# tick-mk-4_2.net
KiCad netlist of a schematic drawn in EAGLE
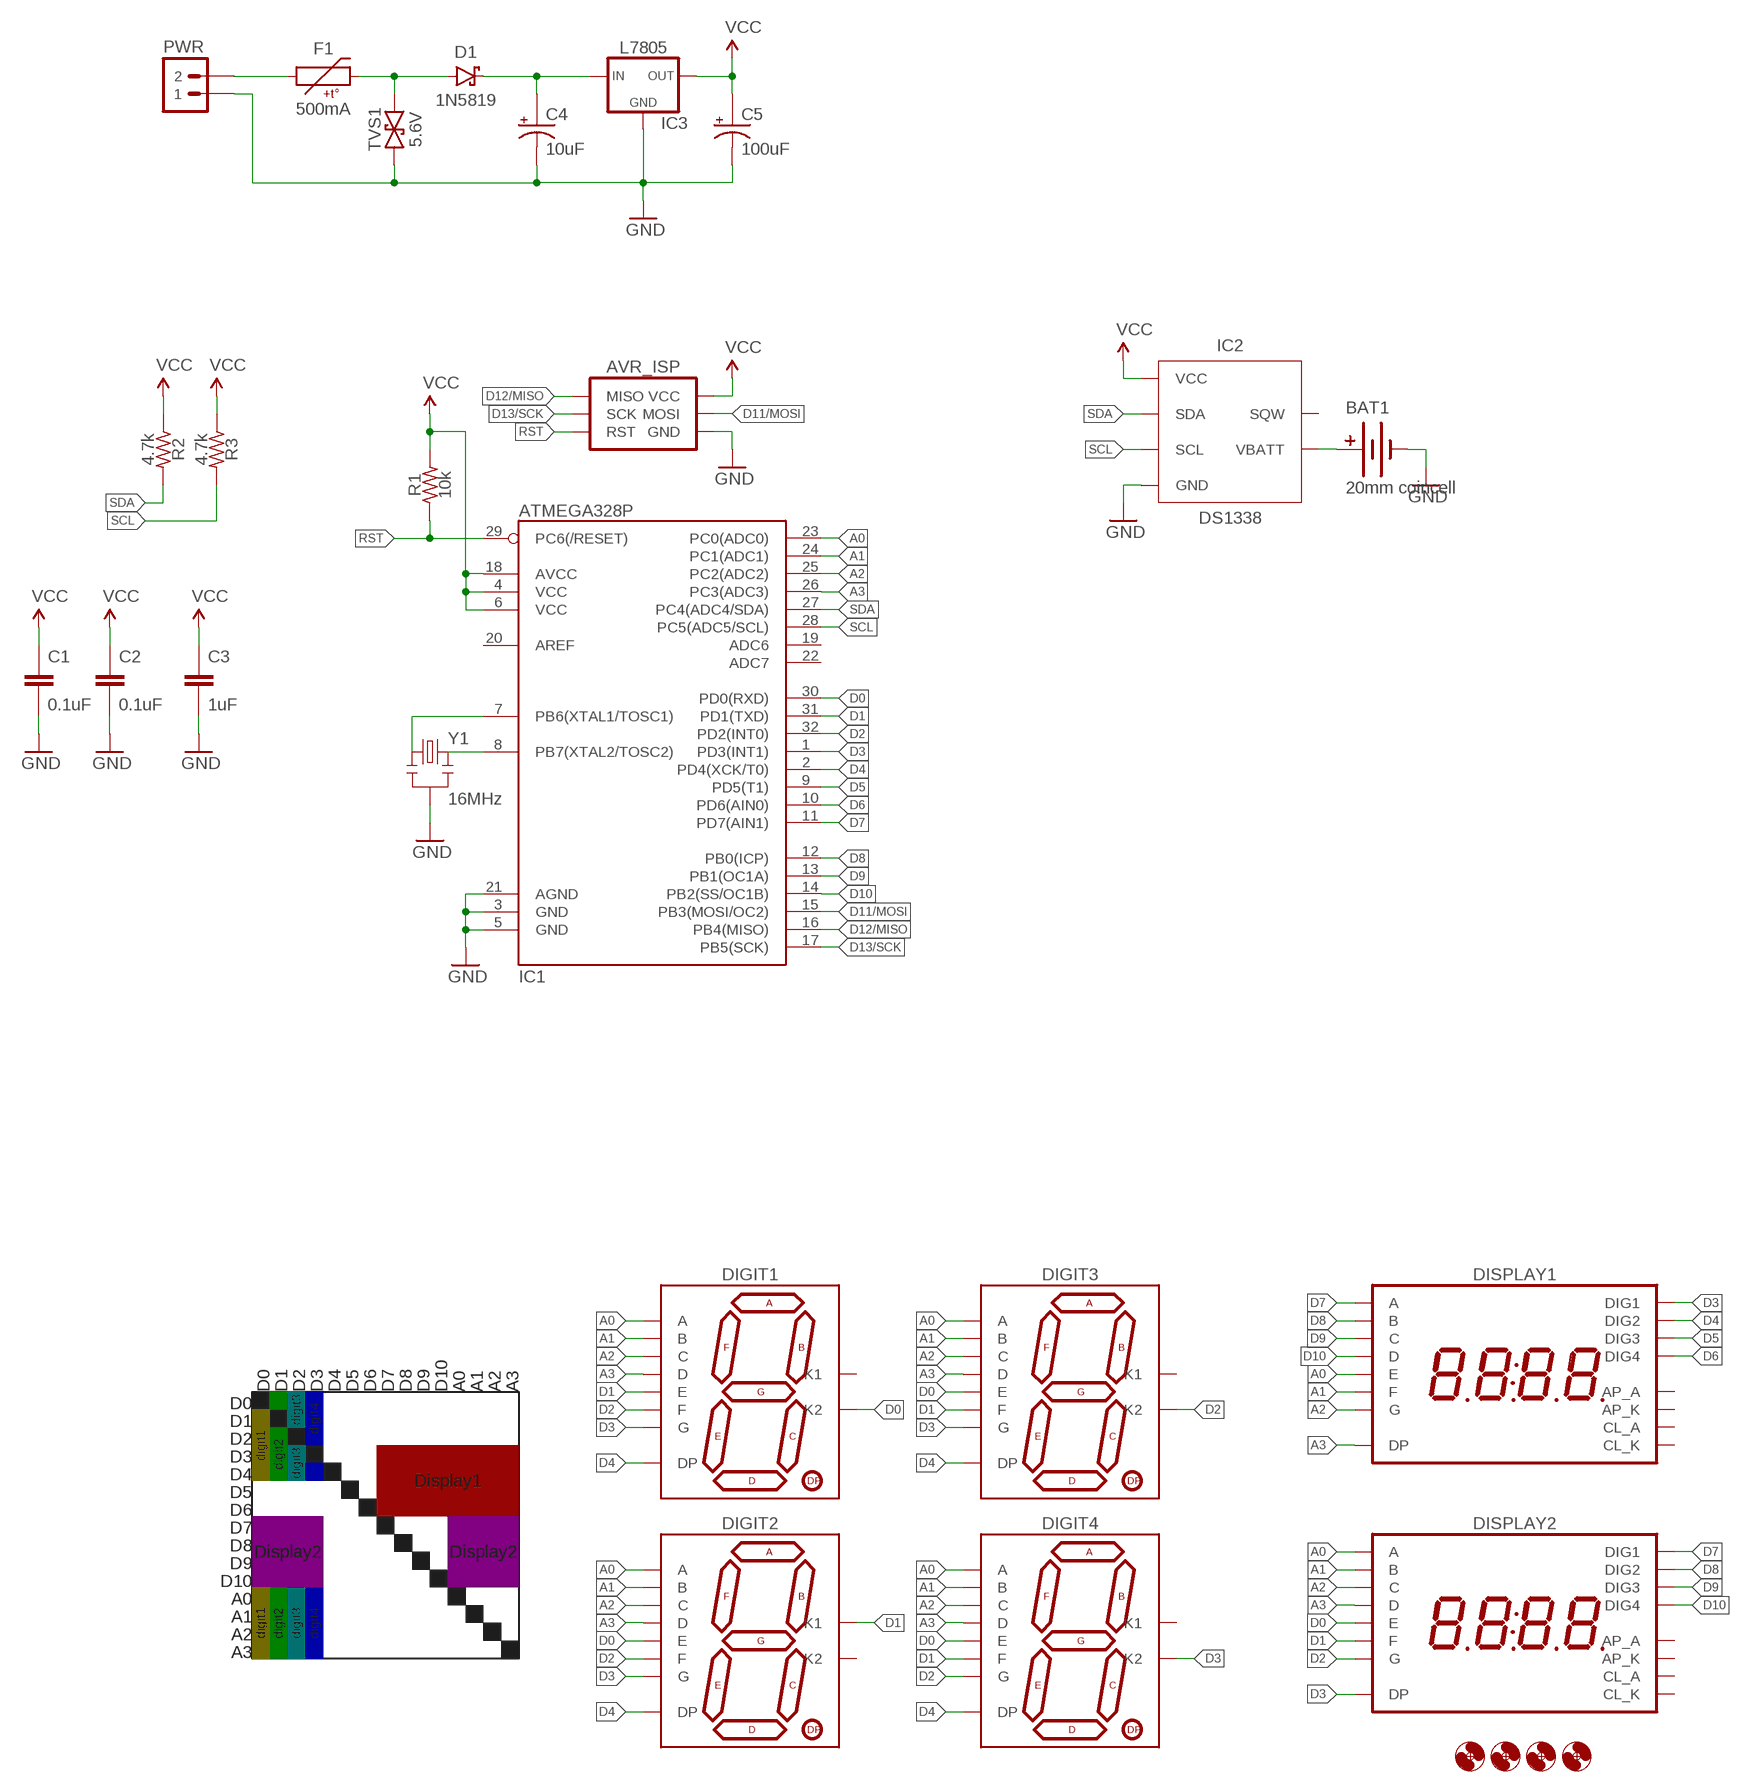
[diagram p0: schematic, sheet 1]

(export (version "E")
  (design (tool "Eeschema 10.0.6"))
  (components
    (comp (ref "AVR_ISP")
      (value "AVR_SPI_PRG_6PTH")
      (footprint "eagle-import:2X3")
      (libsource (lib "eagle-import") (part "AVR_SPI_PRG_6PTH"))
    )
    (comp (ref "BAT1")
      (value "20mm coincell")
      (footprint "eagle-import:BATTCON_20MM_MINE")
      (libsource (lib "eagle-import") (part "BATTERY20MMSMD-MINE"))
    )
    (comp (ref "C1")
      (value "0.1uF")
      (footprint "eagle-import:C025-024X044")
      (libsource (lib "eagle-import") (part "CAPACITOR-CERAMIC025-024X044"))
    )
    (comp (ref "C2")
      (value "0.1uF")
      (footprint "eagle-import:C025-024X044")
      (libsource (lib "eagle-import") (part "CAPACITOR-CERAMIC025-024X044"))
    )
    (comp (ref "C3")
      (value "1uF")
      (footprint "eagle-import:C025-024X044")
      (libsource (lib "eagle-import") (part "CAPACITOR-CERAMIC025-024X044"))
    )
    (comp (ref "C4")
      (value "10uF")
      (footprint "eagle-import:E2-5")
      (libsource (lib "eagle-import") (part "CAPACITOR-POLARIZEDE2-5"))
    )
    (comp (ref "C5")
      (value "100uF")
      (footprint "eagle-import:E2,5-6")
      (libsource (lib "eagle-import") (part "CAPACITOR-POLARIZEDE2.5-6"))
    )
    (comp (ref "D1")
      (value "1N5819")
      (footprint "eagle-import:DIODE-10.16MM")
      (libsource (lib "eagle-import") (part "DIODE-SCHOTTKYPTH-10.16MM"))
    )
    (comp (ref "DIGIT1")
      (value "7SEG_1DIGPTH-25.4MM-BARE")
      (footprint "eagle-import:7SEG_1DIG_25.4MM_NOSILK")
      (libsource (lib "eagle-import") (part "7SEG_1DIGPTH-25.4MM-BARE"))
    )
    (comp (ref "DIGIT2")
      (value "7SEG_1DIGPTH-25.4MM-BARE")
      (footprint "eagle-import:7SEG_1DIG_25.4MM_NOSILK")
      (libsource (lib "eagle-import") (part "7SEG_1DIGPTH-25.4MM-BARE"))
    )
    (comp (ref "DIGIT3")
      (value "7SEG_1DIGPTH-25.4MM-BARE")
      (footprint "eagle-import:7SEG_1DIG_25.4MM_NOSILK")
      (libsource (lib "eagle-import") (part "7SEG_1DIGPTH-25.4MM-BARE"))
    )
    (comp (ref "DIGIT4")
      (value "7SEG_1DIGPTH-25.4MM-BARE")
      (footprint "eagle-import:7SEG_1DIG_25.4MM_NOSILK")
      (libsource (lib "eagle-import") (part "7SEG_1DIGPTH-25.4MM-BARE"))
    )
    (comp (ref "DISPLAY1")
      (value "7SEG_4DIGIT_COLON_APOS")
      (footprint "eagle-import:7SEG_4DIG_10MM")
      (libsource (lib "eagle-import") (part "7SEG_4DIGIT_COLON_APOS"))
    )
    (comp (ref "DISPLAY2")
      (value "7SEG_4DIGIT_COLON_APOS")
      (footprint "eagle-import:7SEG_4DIG_10MM")
      (libsource (lib "eagle-import") (part "7SEG_4DIGIT_COLON_APOS"))
    )
    (comp (ref "F1")
      (value "500mA")
      (footprint "eagle-import:PTC-PTH-5.08MM")
      (libsource (lib "eagle-import") (part "PTCPTH-5.08MM"))
    )
    (comp (ref "H1")
      (value "HOLE#2")
      (footprint "eagle-import:HOLE-#2")
      (libsource (lib "eagle-import") (part "HOLE#2"))
    )
    (comp (ref "H2")
      (value "HOLE#2")
      (footprint "eagle-import:HOLE-#2")
      (libsource (lib "eagle-import") (part "HOLE#2"))
    )
    (comp (ref "H3")
      (value "HOLE#2")
      (footprint "eagle-import:HOLE-#2")
      (libsource (lib "eagle-import") (part "HOLE#2"))
    )
    (comp (ref "H4")
      (value "HOLE#2")
      (footprint "eagle-import:HOLE-#2")
      (libsource (lib "eagle-import") (part "HOLE#2"))
    )
    (comp (ref "IC1")
      (value "ATMEGA328P")
      (footprint "eagle-import:TQFP32-08")
      (libsource (lib "eagle-import") (part "ATMEGA328_SMT"))
    )
    (comp (ref "IC2")
      (value "DS1338")
      (footprint "eagle-import:SO16W")
      (libsource (lib "eagle-import") (part "DS1338CSOIC16W"))
    )
    (comp (ref "IC3")
      (value "L7805")
      (footprint "eagle-import:TO220-IGO-THERMPAD")
      (libsource (lib "eagle-import") (part "V_REG_78XXTO-220-THERMPAD"))
    )
    (comp (ref "PWR")
      (value "M02JST-PTH-VERT")
      (footprint "eagle-import:JST-2-PH-VERT-PTH")
      (libsource (lib "eagle-import") (part "M02JST-PTH-VERT"))
    )
    (comp (ref "R1")
      (value "10k")
      (footprint "eagle-import:RESISTOR-AXIAL-PTH-6.35MM")
      (libsource (lib "eagle-import") (part "RESISTORPTH-AXIAL-6.35MM"))
    )
    (comp (ref "R2")
      (value "4.7k")
      (footprint "eagle-import:RESISTOR-AXIAL-PTH-6.35MM")
      (libsource (lib "eagle-import") (part "RESISTORPTH-AXIAL-6.35MM"))
    )
    (comp (ref "R3")
      (value "4.7k")
      (footprint "eagle-import:RESISTOR-AXIAL-PTH-6.35MM")
      (libsource (lib "eagle-import") (part "RESISTORPTH-AXIAL-6.35MM"))
    )
    (comp (ref "TVS1")
      (value "5.6V")
      (footprint "eagle-import:DO-41-TVS-BI-10.16MM")
      (libsource (lib "eagle-import") (part "TVSDO-41-10.16MM"))
    )
    (comp (ref "Y1")
      (value "16MHz")
      (footprint "eagle-import:RESONATOR-PTH")
      (libsource (lib "eagle-import") (part "RESONATORPTH"))
    )
  )
  (nets
    (net (code "1") (name "A0") (class "Default")
      (node (ref "DIGIT1") (pin "7") (pinfunction "A_7") (pintype "bidirectional"))
      (node (ref "DIGIT2") (pin "7") (pinfunction "A_7") (pintype "bidirectional"))
      (node (ref "DIGIT3") (pin "7") (pinfunction "A_7") (pintype "bidirectional"))
      (node (ref "DIGIT4") (pin "7") (pinfunction "A_7") (pintype "bidirectional"))
      (node (ref "DISPLAY1") (pin "5") (pinfunction "E_5") (pintype "passive"))
      (node (ref "DISPLAY2") (pin "14") (pinfunction "A_14") (pintype "passive"))
      (node (ref "IC1") (pin "23") (pinfunction "PC0(ADC0)_23") (pintype "bidirectional"))
    )
    (net (code "2") (name "A1") (class "Default")
      (node (ref "DIGIT1") (pin "6") (pinfunction "B_6") (pintype "bidirectional"))
      (node (ref "DIGIT2") (pin "6") (pinfunction "B_6") (pintype "bidirectional"))
      (node (ref "DIGIT3") (pin "6") (pinfunction "B_6") (pintype "bidirectional"))
      (node (ref "DIGIT4") (pin "6") (pinfunction "B_6") (pintype "bidirectional"))
      (node (ref "DISPLAY1") (pin "11") (pinfunction "F_11") (pintype "passive"))
      (node (ref "DISPLAY2") (pin "16") (pinfunction "B_16") (pintype "passive"))
      (node (ref "IC1") (pin "24") (pinfunction "PC1(ADC1)_24") (pintype "bidirectional"))
    )
    (net (code "3") (name "A2") (class "Default")
      (node (ref "DIGIT1") (pin "4") (pinfunction "C_4") (pintype "bidirectional"))
      (node (ref "DIGIT2") (pin "4") (pinfunction "C_4") (pintype "bidirectional"))
      (node (ref "DIGIT3") (pin "4") (pinfunction "C_4") (pintype "bidirectional"))
      (node (ref "DIGIT4") (pin "4") (pinfunction "C_4") (pintype "bidirectional"))
      (node (ref "DISPLAY1") (pin "15") (pinfunction "G_15") (pintype "passive"))
      (node (ref "DISPLAY2") (pin "13") (pinfunction "C_13") (pintype "passive"))
      (node (ref "IC1") (pin "25") (pinfunction "PC2(ADC2)_25") (pintype "bidirectional"))
    )
    (net (code "4") (name "A3") (class "Default")
      (node (ref "DIGIT1") (pin "2") (pinfunction "D_2") (pintype "bidirectional"))
      (node (ref "DIGIT2") (pin "2") (pinfunction "D_2") (pintype "bidirectional"))
      (node (ref "DIGIT3") (pin "2") (pinfunction "D_2") (pintype "bidirectional"))
      (node (ref "DIGIT4") (pin "2") (pinfunction "D_2") (pintype "bidirectional"))
      (node (ref "DISPLAY1") (pin "7") (pinfunction "DP_7") (pintype "passive"))
      (node (ref "DISPLAY2") (pin "3") (pinfunction "D_3") (pintype "passive"))
      (node (ref "IC1") (pin "26") (pinfunction "PC3(ADC3)_26") (pintype "bidirectional"))
    )
    (net (code "5") (name "D0") (class "Default")
      (node (ref "DIGIT1") (pin "8") (pinfunction "K2_8") (pintype "bidirectional"))
      (node (ref "DIGIT2") (pin "1") (pinfunction "E_1") (pintype "bidirectional"))
      (node (ref "DIGIT3") (pin "1") (pinfunction "E_1") (pintype "bidirectional"))
      (node (ref "DIGIT4") (pin "1") (pinfunction "E_1") (pintype "bidirectional"))
      (node (ref "DISPLAY2") (pin "5") (pinfunction "E_5") (pintype "passive"))
      (node (ref "IC1") (pin "30") (pinfunction "PD0(RXD)_30") (pintype "bidirectional"))
    )
    (net (code "6") (name "D1") (class "Default")
      (node (ref "DIGIT1") (pin "1") (pinfunction "E_1") (pintype "bidirectional"))
      (node (ref "DIGIT2") (pin "3") (pinfunction "K1_3") (pintype "bidirectional"))
      (node (ref "DIGIT3") (pin "9") (pinfunction "F_9") (pintype "bidirectional"))
      (node (ref "DIGIT4") (pin "9") (pinfunction "F_9") (pintype "bidirectional"))
      (node (ref "DISPLAY2") (pin "11") (pinfunction "F_11") (pintype "passive"))
      (node (ref "IC1") (pin "31") (pinfunction "PD1(TXD)_31") (pintype "bidirectional"))
    )
    (net (code "7") (name "D2") (class "Default")
      (node (ref "DIGIT1") (pin "9") (pinfunction "F_9") (pintype "bidirectional"))
      (node (ref "DIGIT2") (pin "9") (pinfunction "F_9") (pintype "bidirectional"))
      (node (ref "DIGIT3") (pin "8") (pinfunction "K2_8") (pintype "bidirectional"))
      (node (ref "DIGIT4") (pin "10") (pinfunction "G_10") (pintype "bidirectional"))
      (node (ref "DISPLAY2") (pin "15") (pinfunction "G_15") (pintype "passive"))
      (node (ref "IC1") (pin "32") (pinfunction "PD2(INT0)_32") (pintype "bidirectional"))
    )
    (net (code "8") (name "D3") (class "Default")
      (node (ref "DIGIT1") (pin "10") (pinfunction "G_10") (pintype "bidirectional"))
      (node (ref "DIGIT2") (pin "10") (pinfunction "G_10") (pintype "bidirectional"))
      (node (ref "DIGIT3") (pin "10") (pinfunction "G_10") (pintype "bidirectional"))
      (node (ref "DIGIT4") (pin "8") (pinfunction "K2_8") (pintype "bidirectional"))
      (node (ref "DISPLAY1") (pin "1") (pinfunction "DIG1_1") (pintype "passive"))
      (node (ref "DISPLAY2") (pin "7") (pinfunction "DP_7") (pintype "passive"))
      (node (ref "IC1") (pin "1") (pinfunction "PD3(INT1)_1") (pintype "bidirectional"))
    )
    (net (code "9") (name "D4") (class "Default")
      (node (ref "DIGIT1") (pin "5") (pinfunction "DP_5") (pintype "bidirectional"))
      (node (ref "DIGIT2") (pin "5") (pinfunction "DP_5") (pintype "bidirectional"))
      (node (ref "DIGIT3") (pin "5") (pinfunction "DP_5") (pintype "bidirectional"))
      (node (ref "DIGIT4") (pin "5") (pinfunction "DP_5") (pintype "bidirectional"))
      (node (ref "DISPLAY1") (pin "2") (pinfunction "DIG2_2") (pintype "passive"))
      (node (ref "IC1") (pin "2") (pinfunction "PD4(XCK/T0)_2") (pintype "bidirectional"))
    )
    (net (code "10") (name "D5") (class "Default")
      (node (ref "DISPLAY1") (pin "6") (pinfunction "DIG3_6") (pintype "passive"))
      (node (ref "IC1") (pin "9") (pinfunction "PD5(T1)_9") (pintype "bidirectional"))
    )
    (net (code "11") (name "D6") (class "Default")
      (node (ref "DISPLAY1") (pin "8") (pinfunction "DIG4_8") (pintype "passive"))
      (node (ref "IC1") (pin "10") (pinfunction "PD6(AIN0)_10") (pintype "bidirectional"))
    )
    (net (code "12") (name "D7") (class "Default")
      (node (ref "DISPLAY1") (pin "14") (pinfunction "A_14") (pintype "passive"))
      (node (ref "DISPLAY2") (pin "1") (pinfunction "DIG1_1") (pintype "passive"))
      (node (ref "IC1") (pin "11") (pinfunction "PD7(AIN1)_11") (pintype "bidirectional"))
    )
    (net (code "13") (name "D8") (class "Default")
      (node (ref "DISPLAY1") (pin "16") (pinfunction "B_16") (pintype "passive"))
      (node (ref "DISPLAY2") (pin "2") (pinfunction "DIG2_2") (pintype "passive"))
      (node (ref "IC1") (pin "12") (pinfunction "PB0(ICP)_12") (pintype "bidirectional"))
    )
    (net (code "14") (name "D9") (class "Default")
      (node (ref "DISPLAY1") (pin "13") (pinfunction "C_13") (pintype "passive"))
      (node (ref "DISPLAY2") (pin "6") (pinfunction "DIG3_6") (pintype "passive"))
      (node (ref "IC1") (pin "13") (pinfunction "PB1(OC1A)_13") (pintype "bidirectional"))
    )
    (net (code "15") (name "D10") (class "Default")
      (node (ref "DISPLAY1") (pin "3") (pinfunction "D_3") (pintype "passive"))
      (node (ref "DISPLAY2") (pin "8") (pinfunction "DIG4_8") (pintype "passive"))
      (node (ref "IC1") (pin "14") (pinfunction "PB2(SS/OC1B)_14") (pintype "bidirectional"))
    )
    (net (code "16") (name "D11{slash}MOSI") (class "Default")
      (node (ref "AVR_ISP") (pin "4") (pinfunction "MOSI_4") (pintype "passive"))
      (node (ref "IC1") (pin "15") (pinfunction "PB3(MOSI/OC2)_15") (pintype "bidirectional"))
    )
    (net (code "17") (name "D12{slash}MISO") (class "Default")
      (node (ref "AVR_ISP") (pin "1") (pinfunction "MISO_1") (pintype "passive"))
      (node (ref "IC1") (pin "16") (pinfunction "PB4(MISO)_16") (pintype "bidirectional"))
    )
    (net (code "18") (name "D13{slash}SCK") (class "Default")
      (node (ref "AVR_ISP") (pin "3") (pinfunction "SCK_3") (pintype "passive"))
      (node (ref "IC1") (pin "17") (pinfunction "PB5(SCK)_17") (pintype "bidirectional"))
    )
    (net (code "19") (name "GND") (class "Default")
      (node (ref "AVR_ISP") (pin "6") (pinfunction "GND_6") (pintype "passive"))
      (node (ref "BAT1") (pin "BOTTOM") (pinfunction "-_BOTTOM") (pintype "power_in"))
      (node (ref "C1") (pin "2") (pinfunction "2_2") (pintype "passive"))
      (node (ref "C2") (pin "2") (pinfunction "2_2") (pintype "passive"))
      (node (ref "C3") (pin "2") (pinfunction "2_2") (pintype "passive"))
      (node (ref "C4") (pin "-") (pinfunction "-_-") (pintype "passive"))
      (node (ref "C5") (pin "-") (pinfunction "-_-") (pintype "passive"))
      (node (ref "IC1") (pin "21") (pinfunction "AGND_21") (pintype "bidirectional"))
      (node (ref "IC1") (pin "3") (pinfunction "GND_3") (pintype "bidirectional"))
      (node (ref "IC1") (pin "5") (pinfunction "GND_5") (pintype "bidirectional"))
      (node (ref "IC2") (pin "10") (pinfunction "GND_10") (pintype "bidirectional"))
      (node (ref "IC2") (pin "11") (pinfunction "GND_11") (pintype "bidirectional"))
      (node (ref "IC2") (pin "12") (pinfunction "GND_12") (pintype "bidirectional"))
      (node (ref "IC2") (pin "13") (pinfunction "GND_13") (pintype "bidirectional"))
      (node (ref "IC2") (pin "15") (pinfunction "GND_15") (pintype "bidirectional"))
      (node (ref "IC2") (pin "4") (pinfunction "GND_4") (pintype "bidirectional"))
      (node (ref "IC2") (pin "5") (pinfunction "GND_5") (pintype "bidirectional"))
      (node (ref "IC2") (pin "6") (pinfunction "GND_6") (pintype "bidirectional"))
      (node (ref "IC2") (pin "7") (pinfunction "GND_7") (pintype "bidirectional"))
      (node (ref "IC2") (pin "8") (pinfunction "GND_8") (pintype "bidirectional"))
      (node (ref "IC2") (pin "9") (pinfunction "GND_9") (pintype "bidirectional"))
      (node (ref "IC3") (pin "4") (pinfunction "GND_4") (pintype "bidirectional"))
      (node (ref "IC3") (pin "GND") (pinfunction "GND_GND") (pintype "bidirectional"))
      (node (ref "PWR") (pin "1") (pinfunction "1_1") (pintype "passive"))
      (node (ref "TVS1") (pin "P$1") (pinfunction "1_P$1") (pintype "passive"))
      (node (ref "Y1") (pin "2") (pinfunction "2_2") (pintype "passive"))
    )
    (net (code "20") (name "Net-(C4-Pad+)") (class "Default")
      (node (ref "C4") (pin "+") (pinfunction "+_+") (pintype "passive"))
      (node (ref "D1") (pin "C") (pinfunction "C_C") (pintype "passive"))
      (node (ref "IC3") (pin "IN") (pinfunction "IN_IN") (pintype "bidirectional"))
    )
    (net (code "21") (name "Net-(F1-1)") (class "Default")
      (node (ref "F1") (pin "P$1") (pinfunction "1_P$1") (pintype "passive"))
      (node (ref "PWR") (pin "2") (pinfunction "2_2") (pintype "passive"))
    )
    (net (code "22") (name "Net-(F1-2)") (class "Default")
      (node (ref "D1") (pin "A") (pinfunction "A_A") (pintype "passive"))
      (node (ref "F1") (pin "P$2") (pinfunction "2_P$2") (pintype "passive"))
      (node (ref "TVS1") (pin "P$2") (pinfunction "2_P$2") (pintype "passive"))
    )
    (net (code "23") (name "Net-(IC1-PB6(XTAL1{slash}TOSC1))") (class "Default")
      (node (ref "IC1") (pin "7") (pinfunction "PB6(XTAL1/TOSC1)_7") (pintype "bidirectional"))
      (node (ref "Y1") (pin "1") (pinfunction "1_1") (pintype "passive"))
    )
    (net (code "24") (name "Net-(IC1-PB7(XTAL2{slash}TOSC2))") (class "Default")
      (node (ref "IC1") (pin "8") (pinfunction "PB7(XTAL2/TOSC2)_8") (pintype "bidirectional"))
      (node (ref "Y1") (pin "3") (pinfunction "3_3") (pintype "passive"))
    )
    (net (code "25") (name "Net-(IC2-VBATT)") (class "Default")
      (node (ref "BAT1") (pin "TOP@1") (pinfunction "+_TOP@1") (pintype "power_in"))
      (node (ref "BAT1") (pin "TOP@2") (pinfunction "+_TOP@2") (pintype "power_in"))
      (node (ref "IC2") (pin "14") (pinfunction "VBATT_14") (pintype "bidirectional"))
    )
    (net (code "26") (name "RST") (class "Default")
      (node (ref "AVR_ISP") (pin "5") (pinfunction "RST_5") (pintype "passive"))
      (node (ref "IC1") (pin "29") (pinfunction "PC6(/RESET)_29") (pintype "bidirectional"))
      (node (ref "R1") (pin "P$1") (pinfunction "1_P$1") (pintype "passive"))
    )
    (net (code "27") (name "SCL") (class "Default")
      (node (ref "IC1") (pin "28") (pinfunction "PC5(ADC5/SCL)_28") (pintype "bidirectional"))
      (node (ref "IC2") (pin "1") (pinfunction "SCL_1") (pintype "bidirectional"))
      (node (ref "R3") (pin "P$2") (pinfunction "2_P$2") (pintype "passive"))
    )
    (net (code "28") (name "SDA") (class "Default")
      (node (ref "IC1") (pin "27") (pinfunction "PC4(ADC4/SDA)_27") (pintype "bidirectional"))
      (node (ref "IC2") (pin "16") (pinfunction "SDA_16") (pintype "bidirectional"))
      (node (ref "R2") (pin "P$2") (pinfunction "2_P$2") (pintype "passive"))
    )
    (net (code "29") (name "VCC") (class "Default")
      (node (ref "AVR_ISP") (pin "2") (pinfunction "VCC_2") (pintype "passive"))
      (node (ref "C1") (pin "1") (pinfunction "1_1") (pintype "passive"))
      (node (ref "C2") (pin "1") (pinfunction "1_1") (pintype "passive"))
      (node (ref "C3") (pin "1") (pinfunction "1_1") (pintype "passive"))
      (node (ref "C5") (pin "+") (pinfunction "+_+") (pintype "passive"))
      (node (ref "IC1") (pin "18") (pinfunction "AVCC_18") (pintype "bidirectional"))
      (node (ref "IC1") (pin "4") (pinfunction "VCC_4") (pintype "bidirectional"))
      (node (ref "IC1") (pin "6") (pinfunction "VCC_6") (pintype "bidirectional"))
      (node (ref "IC2") (pin "3") (pinfunction "VCC_3") (pintype "bidirectional"))
      (node (ref "IC3") (pin "OUT") (pinfunction "OUT_OUT") (pintype "bidirectional"))
      (node (ref "R1") (pin "P$2") (pinfunction "2_P$2") (pintype "passive"))
      (node (ref "R2") (pin "P$1") (pinfunction "1_P$1") (pintype "passive"))
      (node (ref "R3") (pin "P$1") (pinfunction "1_P$1") (pintype "passive"))
    )
    (net (code "30") (name "unconnected-(DIGIT1-K1-Pad3)") (class "Default")
      (node (ref "DIGIT1") (pin "3") (pinfunction "K1_3") (pintype "bidirectional"))
    )
    (net (code "31") (name "unconnected-(DIGIT2-K2-Pad8)") (class "Default")
      (node (ref "DIGIT2") (pin "8") (pinfunction "K2_8") (pintype "bidirectional"))
    )
    (net (code "32") (name "unconnected-(DIGIT3-K1-Pad3)") (class "Default")
      (node (ref "DIGIT3") (pin "3") (pinfunction "K1_3") (pintype "bidirectional"))
    )
    (net (code "33") (name "unconnected-(DIGIT4-K1-Pad3)") (class "Default")
      (node (ref "DIGIT4") (pin "3") (pinfunction "K1_3") (pintype "bidirectional"))
    )
    (net (code "34") (name "unconnected-(DISPLAY1-AP_A-Pad10)") (class "Default")
      (node (ref "DISPLAY1") (pin "10") (pinfunction "AP_A_10") (pintype "bidirectional"))
    )
    (net (code "35") (name "unconnected-(DISPLAY1-AP_K-Pad9)") (class "Default")
      (node (ref "DISPLAY1") (pin "9") (pinfunction "AP_K_9") (pintype "bidirectional"))
    )
    (net (code "36") (name "unconnected-(DISPLAY1-CL_A-Pad4)") (class "Default")
      (node (ref "DISPLAY1") (pin "4") (pinfunction "CL_A_4") (pintype "passive"))
    )
    (net (code "37") (name "unconnected-(DISPLAY1-CL_K-Pad12)") (class "Default")
      (node (ref "DISPLAY1") (pin "12") (pinfunction "CL_K_12") (pintype "passive"))
    )
    (net (code "38") (name "unconnected-(DISPLAY2-AP_A-Pad10)") (class "Default")
      (node (ref "DISPLAY2") (pin "10") (pinfunction "AP_A_10") (pintype "bidirectional"))
    )
    (net (code "39") (name "unconnected-(DISPLAY2-AP_K-Pad9)") (class "Default")
      (node (ref "DISPLAY2") (pin "9") (pinfunction "AP_K_9") (pintype "bidirectional"))
    )
    (net (code "40") (name "unconnected-(DISPLAY2-CL_A-Pad4)") (class "Default")
      (node (ref "DISPLAY2") (pin "4") (pinfunction "CL_A_4") (pintype "passive"))
    )
    (net (code "41") (name "unconnected-(DISPLAY2-CL_K-Pad12)") (class "Default")
      (node (ref "DISPLAY2") (pin "12") (pinfunction "CL_K_12") (pintype "passive"))
    )
    (net (code "42") (name "unconnected-(IC1-ADC6-Pad19)") (class "Default")
      (node (ref "IC1") (pin "19") (pinfunction "ADC6_19") (pintype "bidirectional"))
    )
    (net (code "43") (name "unconnected-(IC1-ADC7-Pad22)") (class "Default")
      (node (ref "IC1") (pin "22") (pinfunction "ADC7_22") (pintype "bidirectional"))
    )
    (net (code "44") (name "unconnected-(IC1-AREF-Pad20)") (class "Default")
      (node (ref "IC1") (pin "20") (pinfunction "AREF_20") (pintype "bidirectional"))
    )
    (net (code "45") (name "unconnected-(IC2-SQW-Pad2)") (class "Default")
      (node (ref "IC2") (pin "2") (pinfunction "SQW_2") (pintype "bidirectional"))
    )
  )
)
